# Me-Infrared_Reciver_Decode_v2_0.net
KiCad netlist of a schematic drawn in EAGLE
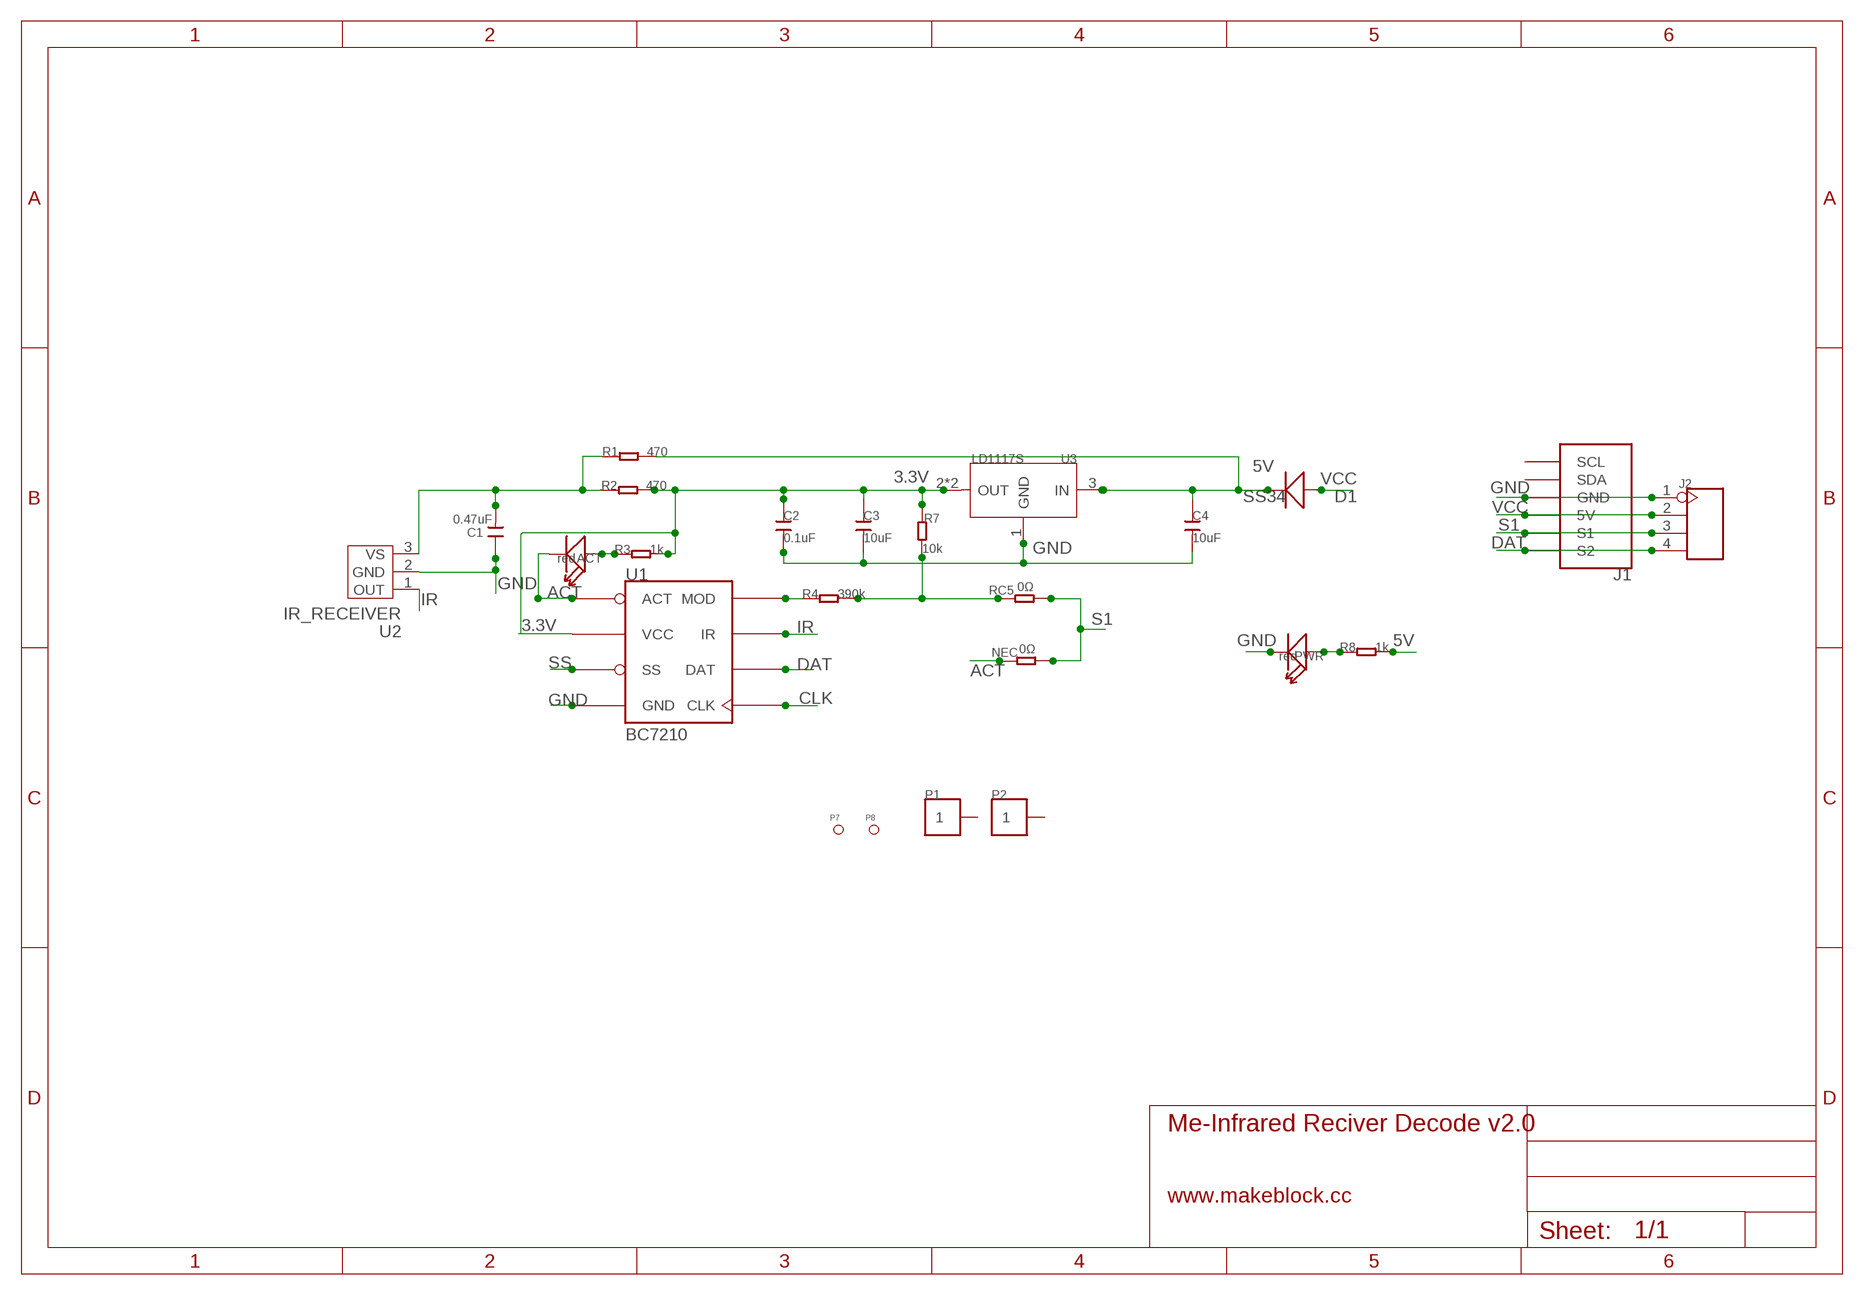
[diagram p0: schematic, sheet 1]

(export (version "E")
  (design (tool "Eeschema 10.0.6"))
  (components
    (comp (ref "ACT")
      (value "red")
      (footprint "eagle-import:LED-0603")
      (libsource (lib "eagle-import") (part "LED'0603'"))
    )
    (comp (ref "C1")
      (value "0.47uF")
      (footprint "eagle-import:0603")
      (libsource (lib "eagle-import") (part "C-0603"))
    )
    (comp (ref "C2")
      (value "0.1uF")
      (footprint "eagle-import:0603")
      (libsource (lib "eagle-import") (part "C-0603"))
    )
    (comp (ref "C3")
      (value "10uF")
      (footprint "eagle-import:0603")
      (libsource (lib "eagle-import") (part "C-0603"))
    )
    (comp (ref "C4")
      (value "10uF")
      (footprint "eagle-import:0603")
      (libsource (lib "eagle-import") (part "C-0603"))
    )
    (comp (ref "D1")
      (value "SS34")
      (footprint "eagle-import:D2010")
      (libsource (lib "eagle-import") (part "D'SMA'"))
    )
    (comp (ref "J1")
      (value "RJ11-6P6C-DIGI")
      (footprint "eagle-import:RJ11-6P6C")
      (libsource (lib "eagle-import") (part "RJ11-6P6C-DIGI"))
    )
    (comp (ref "J2")
      (value "HEADER-4P-60/35MIL")
      (footprint "eagle-import:4P-65_35MIL")
      (libsource (lib "eagle-import") (part "HEADER-4P-60/35MIL"))
    )
    (comp (ref "NEC")
      (value "0Ω")
      (footprint "eagle-import:0603")
      (libsource (lib "eagle-import") (part "R-0603"))
    )
    (comp (ref "P1")
      (value "PAD-1P-4MM")
      (footprint "eagle-import:HOLE-01")
      (libsource (lib "eagle-import") (part "PAD-1P-4MM"))
    )
    (comp (ref "P2")
      (value "PAD-1P-4MM")
      (footprint "eagle-import:HOLE-01")
      (libsource (lib "eagle-import") (part "PAD-1P-4MM"))
    )
    (comp (ref "P7")
      (value "PAD-MARK")
      (footprint "eagle-import:ROUND-MARK-1.0")
      (fields (field (name "PARTNO") "DNP"))
      (libsource (lib "eagle-import") (part "PAD-MARK"))
    )
    (comp (ref "P8")
      (value "PAD-MARK")
      (footprint "eagle-import:ROUND-MARK-1.0")
      (fields (field (name "PARTNO") "DNP"))
      (libsource (lib "eagle-import") (part "PAD-MARK"))
    )
    (comp (ref "PWR")
      (value "red")
      (footprint "eagle-import:LED-0603")
      (libsource (lib "eagle-import") (part "LED'0603'"))
    )
    (comp (ref "R1")
      (value "470")
      (footprint "eagle-import:0603")
      (libsource (lib "eagle-import") (part "R-0603"))
    )
    (comp (ref "R2")
      (value "470")
      (footprint "eagle-import:0603")
      (libsource (lib "eagle-import") (part "R-0603"))
    )
    (comp (ref "R3")
      (value "1k")
      (footprint "eagle-import:0603")
      (libsource (lib "eagle-import") (part "R-0603"))
    )
    (comp (ref "R4")
      (value "390k")
      (footprint "eagle-import:0603")
      (libsource (lib "eagle-import") (part "R-0603"))
    )
    (comp (ref "R7")
      (value "10k")
      (footprint "eagle-import:0603")
      (libsource (lib "eagle-import") (part "R-0603"))
    )
    (comp (ref "R8")
      (value "1k")
      (footprint "eagle-import:0603")
      (libsource (lib "eagle-import") (part "R-0603"))
    )
    (comp (ref "RC5")
      (value "0Ω")
      (footprint "eagle-import:0603")
      (libsource (lib "eagle-import") (part "R-0603"))
    )
    (comp (ref "U1")
      (value "BC7210")
      (footprint "eagle-import:BC7210")
      (libsource (lib "eagle-import") (part "BC7210"))
    )
    (comp (ref "U2")
      (value "IR_RECEIVER")
      (footprint "eagle-import:IR_RECEIVER")
      (libsource (lib "eagle-import") (part "IR_RECEIVER"))
    )
    (comp (ref "U3")
      (value "LD1117S")
      (footprint "eagle-import:SOT-223")
      (libsource (lib "eagle-import") (part "LD1117S"))
    )
  )
  (nets
    (net (code "1") (name "/3.3V") (class "Default")
      (node (ref "C2") (pin "1") (pinfunction "1_1") (pintype "passive"))
      (node (ref "C3") (pin "1") (pinfunction "1_1") (pintype "passive"))
      (node (ref "R2") (pin "2") (pinfunction "2_2") (pintype "passive"))
      (node (ref "R3") (pin "2") (pinfunction "2_2") (pintype "passive"))
      (node (ref "R7") (pin "2") (pinfunction "2_2") (pintype "passive"))
      (node (ref "U1") (pin "P$2") (pinfunction "VCC_P$2") (pintype "bidirectional"))
      (node (ref "U3") (pin "2") (pinfunction "OUT_2") (pintype "bidirectional"))
      (node (ref "U3") (pin "TER") (pinfunction "OUT_TER") (pintype "bidirectional"))
    )
    (net (code "2") (name "/5V") (class "Default")
      (node (ref "C4") (pin "1") (pinfunction "1_1") (pintype "passive"))
      (node (ref "D1") (pin "-") (pinfunction "-_-") (pintype "passive"))
      (node (ref "R1") (pin "2") (pinfunction "2_2") (pintype "passive"))
      (node (ref "R8") (pin "2") (pinfunction "2_2") (pintype "passive"))
      (node (ref "U3") (pin "3") (pinfunction "IN_3") (pintype "bidirectional"))
    )
    (net (code "3") (name "/ACT") (class "Default")
      (node (ref "ACT") (pin "-") (pinfunction "-_-") (pintype "passive"))
      (node (ref "NEC") (pin "1") (pinfunction "1_1") (pintype "passive"))
      (node (ref "U1") (pin "P$1") (pinfunction "ACT_P$1") (pintype "bidirectional"))
    )
    (net (code "4") (name "/CLK") (class "Default")
      (node (ref "U1") (pin "P$5") (pinfunction "CLK_P$5") (pintype "bidirectional"))
    )
    (net (code "5") (name "/DAT") (class "Default")
      (node (ref "J1") (pin "6") (pinfunction "S2_6") (pintype "bidirectional"))
      (node (ref "J2") (pin "4") (pinfunction "P$4_4") (pintype "bidirectional"))
      (node (ref "U1") (pin "P$6") (pinfunction "DAT_P$6") (pintype "bidirectional"))
    )
    (net (code "6") (name "/GND") (class "Default")
      (node (ref "C1") (pin "1") (pinfunction "1_1") (pintype "passive"))
      (node (ref "C2") (pin "2") (pinfunction "2_2") (pintype "passive"))
      (node (ref "C3") (pin "2") (pinfunction "2_2") (pintype "passive"))
      (node (ref "C4") (pin "2") (pinfunction "2_2") (pintype "passive"))
      (node (ref "J1") (pin "3") (pinfunction "GND_3") (pintype "bidirectional"))
      (node (ref "J2") (pin "1") (pinfunction "P$1_1") (pintype "bidirectional"))
      (node (ref "PWR") (pin "-") (pinfunction "-_-") (pintype "passive"))
      (node (ref "U1") (pin "P$4") (pinfunction "GND_P$4") (pintype "bidirectional"))
      (node (ref "U2") (pin "2") (pinfunction "GND_2") (pintype "bidirectional"))
      (node (ref "U3") (pin "1") (pinfunction "GND_1") (pintype "bidirectional"))
    )
    (net (code "7") (name "/IR") (class "Default")
      (node (ref "U1") (pin "P$7") (pinfunction "IR_P$7") (pintype "bidirectional"))
      (node (ref "U2") (pin "1") (pinfunction "OUT_1") (pintype "bidirectional"))
    )
    (net (code "8") (name "/S1") (class "Default")
      (node (ref "J1") (pin "5") (pinfunction "S1_5") (pintype "bidirectional"))
      (node (ref "J2") (pin "3") (pinfunction "P$3_3") (pintype "bidirectional"))
      (node (ref "NEC") (pin "2") (pinfunction "2_2") (pintype "passive"))
      (node (ref "RC5") (pin "2") (pinfunction "2_2") (pintype "passive"))
    )
    (net (code "9") (name "/SS") (class "Default")
      (node (ref "U1") (pin "P$3") (pinfunction "SS_P$3") (pintype "bidirectional"))
    )
    (net (code "10") (name "/VCC") (class "Default")
      (node (ref "D1") (pin "+") (pinfunction "+_+") (pintype "passive"))
      (node (ref "J1") (pin "4") (pinfunction "5V_4") (pintype "bidirectional"))
      (node (ref "J2") (pin "2") (pinfunction "P$2_2") (pintype "bidirectional"))
    )
    (net (code "11") (name "Net-(ACT-Pad+)") (class "Default")
      (node (ref "ACT") (pin "+") (pinfunction "+_+") (pintype "passive"))
      (node (ref "R3") (pin "1") (pinfunction "1_1") (pintype "passive"))
    )
    (net (code "12") (name "Net-(PWR-Pad+)") (class "Default")
      (node (ref "PWR") (pin "+") (pinfunction "+_+") (pintype "passive"))
      (node (ref "R8") (pin "1") (pinfunction "1_1") (pintype "passive"))
    )
    (net (code "13") (name "Net-(R4-Pad2)") (class "Default")
      (node (ref "R4") (pin "2") (pinfunction "2_2") (pintype "passive"))
      (node (ref "R7") (pin "1") (pinfunction "1_1") (pintype "passive"))
      (node (ref "RC5") (pin "1") (pinfunction "1_1") (pintype "passive"))
    )
    (net (code "14") (name "Net-(U1-MOD)") (class "Default")
      (node (ref "R4") (pin "1") (pinfunction "1_1") (pintype "passive"))
      (node (ref "U1") (pin "P$8") (pinfunction "MOD_P$8") (pintype "bidirectional"))
    )
    (net (code "15") (name "Net-(U2-VS)") (class "Default")
      (node (ref "C1") (pin "2") (pinfunction "2_2") (pintype "passive"))
      (node (ref "R1") (pin "1") (pinfunction "1_1") (pintype "passive"))
      (node (ref "R2") (pin "1") (pinfunction "1_1") (pintype "passive"))
      (node (ref "U2") (pin "3") (pinfunction "VS_3") (pintype "bidirectional"))
    )
    (net (code "16") (name "unconnected-(J1-SCL-Pad1)") (class "Default")
      (node (ref "J1") (pin "1") (pinfunction "SCL_1") (pintype "bidirectional"))
    )
    (net (code "17") (name "unconnected-(J1-SDA-Pad2)") (class "Default")
      (node (ref "J1") (pin "2") (pinfunction "SDA_2") (pintype "bidirectional"))
    )
    (net (code "18") (name "unconnected-(P1-Pad1)") (class "Default")
      (node (ref "P1") (pin "1") (pinfunction "1_1") (pintype "bidirectional"))
    )
    (net (code "19") (name "unconnected-(P2-Pad1)") (class "Default")
      (node (ref "P2") (pin "1") (pinfunction "1_1") (pintype "bidirectional"))
    )
  )
)
